# Mind-Synchronizing-Generator-PinHdrPotX.net
KiCad netlist of a schematic drawn in EAGLE
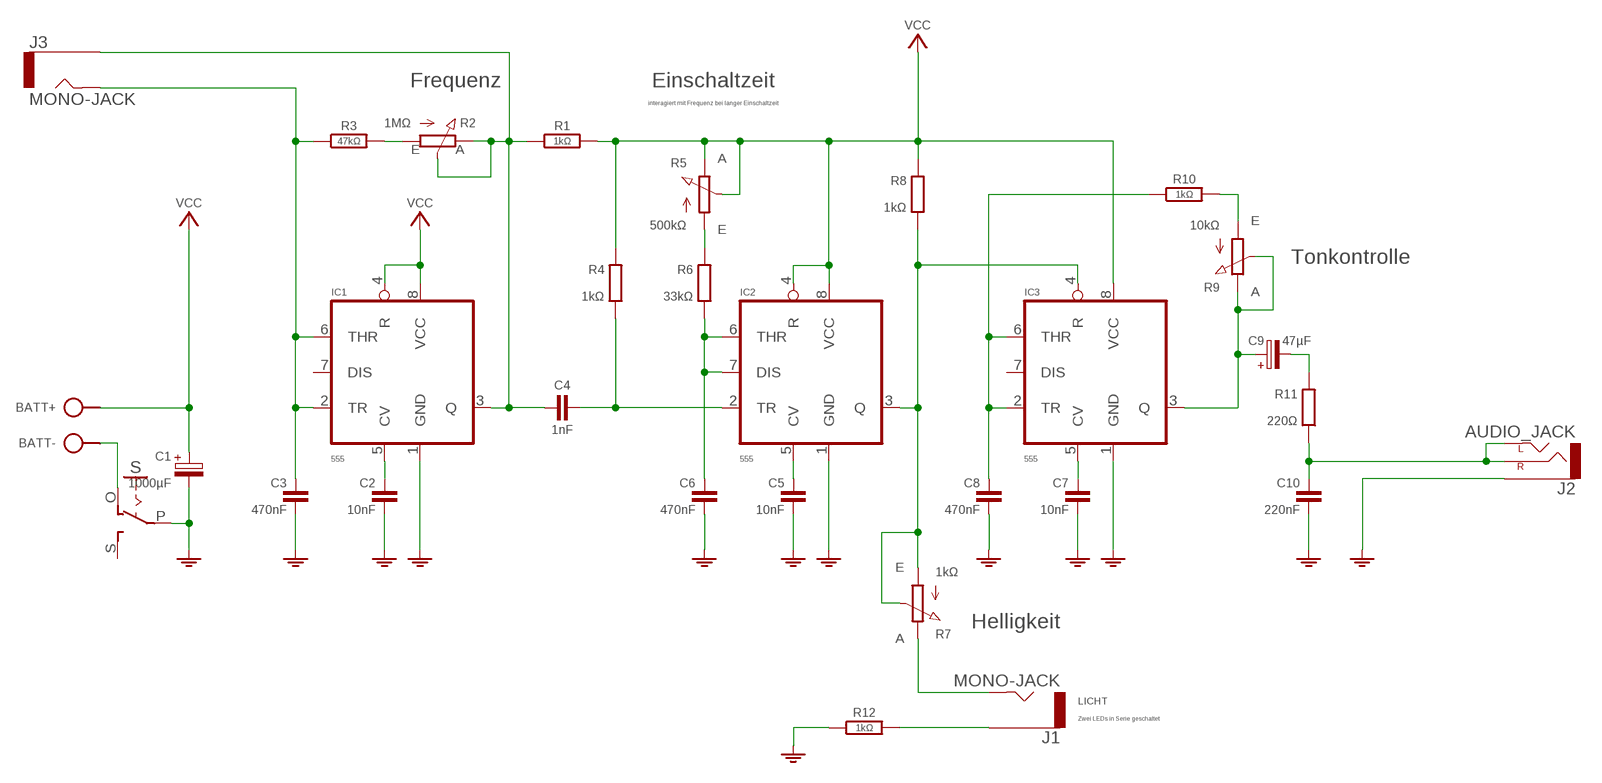
[diagram p0: schematic, sheet 1]

(export (version "E")
  (design (tool "Eeschema 10.0.6"))
  (components
    (comp (ref "BATT")
      (value "SPAD+--+")
      (footprint "eagle-import:SPAD-+")
      (libsource (lib "eagle-import") (part "SPAD+--+"))
    )
    (comp (ref "C1")
      (value "1000µF")
      (footprint "eagle-import:E2,5-6")
      (libsource (lib "eagle-import") (part "CPOLE2.5-6"))
    )
    (comp (ref "C2")
      (value "10nF")
      (footprint "eagle-import:C050-020X044")
      (libsource (lib "eagle-import") (part "C050-020X044"))
    )
    (comp (ref "C3")
      (value "470nF")
      (footprint "eagle-import:C050-040X075")
      (libsource (lib "eagle-import") (part "C050-040X075"))
    )
    (comp (ref "C4")
      (value "1nF")
      (footprint "eagle-import:C050-020X044")
      (libsource (lib "eagle-import") (part "C-H050-020X044"))
    )
    (comp (ref "C5")
      (value "10nF")
      (footprint "eagle-import:C050-020X044_V")
      (libsource (lib "eagle-import") (part "C050-020X044/V"))
    )
    (comp (ref "C6")
      (value "470nF")
      (footprint "eagle-import:C050-040X075")
      (libsource (lib "eagle-import") (part "C050-040X075"))
    )
    (comp (ref "C7")
      (value "10nF")
      (footprint "eagle-import:C075-020X044_V")
      (libsource (lib "eagle-import") (part "C075-020X044/V"))
    )
    (comp (ref "C8")
      (value "470nF")
      (footprint "eagle-import:C050-040X075")
      (libsource (lib "eagle-import") (part "C050-040X075"))
    )
    (comp (ref "C9")
      (value "47µF")
      (footprint "eagle-import:E2,5-4")
      (libsource (lib "eagle-import") (part "CPOL-HE2,5-4"))
    )
    (comp (ref "C10")
      (value "220nF")
      (footprint "eagle-import:C050-025X060")
      (libsource (lib "eagle-import") (part "C025-025X060"))
    )
    (comp (ref "IC1")
      (value "555")
      (footprint "eagle-import:555-DIL")
      (libsource (lib "eagle-import") (part "555_ALT2-LBL"))
    )
    (comp (ref "IC2")
      (value "555")
      (footprint "eagle-import:555-DIL")
      (libsource (lib "eagle-import") (part "555_ALT2-LBL"))
    )
    (comp (ref "IC3")
      (value "555")
      (footprint "eagle-import:555-DIL")
      (libsource (lib "eagle-import") (part "555_ALT2-LBL"))
    )
    (comp (ref "J1")
      (value "MONO-JACK")
      (footprint "eagle-import:STEREOJACK2.5MM_STEREOJACK2.5MM")
      (libsource (lib "eagle-import") (part "MONO-JACK"))
    )
    (comp (ref "J2")
      (value "AUDIO_JACK")
      (footprint "eagle-import:AUDIO-JACK")
      (libsource (lib "eagle-import") (part "AUDIO_JACK"))
    )
    (comp (ref "J3")
      (value "MONO-JACK")
      (footprint "eagle-import:STEREOJACK2.5MM_STEREOJACK2.5MM")
      (libsource (lib "eagle-import") (part "MONO-JACK"))
    )
    (comp (ref "R1")
      (value "1kΩ")
      (footprint "eagle-import:0204_10")
      (libsource (lib "eagle-import") (part "R-H0204/10"))
    )
    (comp (ref "R2")
      (value "1MΩ")
      (footprint "eagle-import:CONN-3P")
      (libsource (lib "eagle-import") (part "POT-H-3P"))
    )
    (comp (ref "R3")
      (value "47kΩ")
      (footprint "eagle-import:0204_10")
      (libsource (lib "eagle-import") (part "R-H0204/10"))
    )
    (comp (ref "R4")
      (value "1kΩ")
      (footprint "eagle-import:0204_10-V")
      (libsource (lib "eagle-import") (part "R0204/10-V"))
    )
    (comp (ref "R5")
      (value "500kΩ")
      (footprint "eagle-import:CONN-3P")
      (libsource (lib "eagle-import") (part "POT-3P"))
    )
    (comp (ref "R6")
      (value "33kΩ")
      (footprint "eagle-import:0204_10")
      (libsource (lib "eagle-import") (part "R0204/10"))
    )
    (comp (ref "R7")
      (value "1kΩ")
      (footprint "eagle-import:CONN-3P")
      (libsource (lib "eagle-import") (part "POT-3P-S1"))
    )
    (comp (ref "R8")
      (value "1kΩ")
      (footprint "eagle-import:0204_10-V")
      (libsource (lib "eagle-import") (part "R0204/10-V"))
    )
    (comp (ref "R9")
      (value "10kΩ")
      (footprint "eagle-import:CONN-3P")
      (libsource (lib "eagle-import") (part "POT-3P"))
    )
    (comp (ref "R10")
      (value "1kΩ")
      (footprint "eagle-import:0204_10")
      (libsource (lib "eagle-import") (part "R-H0204/10"))
    )
    (comp (ref "R11")
      (value "220Ω")
      (footprint "eagle-import:0204_10-V")
      (libsource (lib "eagle-import") (part "R0204/10-V"))
    )
    (comp (ref "R12")
      (value "1kΩ")
      (footprint "eagle-import:0204_10")
      (libsource (lib "eagle-import") (part "R-H0204/10"))
    )
    (comp (ref "S")
      (value "SL-SW-1P-2T-H")
      (footprint "eagle-import:SLSW-1P2T-H")
      (libsource (lib "eagle-import") (part "SL-SW-1P-2T-H"))
    )
  )
  (nets
    (net (code "1") (name "GND") (class "Default")
      (node (ref "C1") (pin "-") (pinfunction "-_-") (pintype "passive"))
      (node (ref "C10") (pin "2") (pinfunction "2_2") (pintype "passive"))
      (node (ref "C2") (pin "2") (pinfunction "2_2") (pintype "passive"))
      (node (ref "C3") (pin "2") (pinfunction "2_2") (pintype "passive"))
      (node (ref "C5") (pin "2") (pinfunction "2_2") (pintype "passive"))
      (node (ref "C6") (pin "2") (pinfunction "2_2") (pintype "passive"))
      (node (ref "C7") (pin "2") (pinfunction "2_2") (pintype "passive"))
      (node (ref "C8") (pin "2") (pinfunction "2_2") (pintype "passive"))
      (node (ref "IC1") (pin "1") (pinfunction "GND_1") (pintype "power_in"))
      (node (ref "IC2") (pin "1") (pinfunction "GND_1") (pintype "power_in"))
      (node (ref "IC3") (pin "1") (pinfunction "GND_1") (pintype "power_in"))
      (node (ref "J2") (pin "SLEEVE") (pinfunction "SLEEVE_SLEEVE") (pintype "bidirectional"))
      (node (ref "R12") (pin "1") (pinfunction "1_1") (pintype "passive"))
      (node (ref "S") (pin "P") (pinfunction "P_P") (pintype "passive"))
    )
    (net (code "2") (name "Net-(BATTB-P$1)") (class "Default")
      (node (ref "BATT") (pin "1") (pinfunction "P$1_1") (pintype "passive"))
      (node (ref "S") (pin "O") (pinfunction "O_O") (pintype "passive"))
    )
    (net (code "3") (name "Net-(IC1-CV)") (class "Default")
      (node (ref "C2") (pin "1") (pinfunction "1_1") (pintype "passive"))
      (node (ref "IC1") (pin "5") (pinfunction "CV_5") (pintype "input"))
    )
    (net (code "4") (name "Net-(IC1-Q)") (class "Default")
      (node (ref "C4") (pin "1") (pinfunction "1_1") (pintype "passive"))
      (node (ref "IC1") (pin "3") (pinfunction "Q_3") (pintype "output"))
      (node (ref "J3") (pin "SHIELD") (pinfunction "SLEEVE_SHIELD") (pintype "bidirectional"))
      (node (ref "R1") (pin "1") (pinfunction "1_1") (pintype "passive"))
      (node (ref "R2") (pin "2") (pinfunction "S_2") (pintype "passive"))
      (node (ref "R2") (pin "3") (pinfunction "E_3") (pintype "passive"))
    )
    (net (code "5") (name "Net-(IC1-THR)") (class "Default")
      (node (ref "C3") (pin "1") (pinfunction "1_1") (pintype "passive"))
      (node (ref "IC1") (pin "2") (pinfunction "TR_2") (pintype "input"))
      (node (ref "IC1") (pin "6") (pinfunction "THR_6") (pintype "input"))
      (node (ref "J3") (pin "TIP") (pinfunction "LEFT_TIP") (pintype "bidirectional"))
      (node (ref "R3") (pin "1") (pinfunction "1_1") (pintype "passive"))
    )
    (net (code "6") (name "Net-(IC2-CV)") (class "Default")
      (node (ref "C5") (pin "1") (pinfunction "1_1") (pintype "passive"))
      (node (ref "IC2") (pin "5") (pinfunction "CV_5") (pintype "input"))
    )
    (net (code "7") (name "Net-(IC2-DIS)") (class "Default")
      (node (ref "C6") (pin "1") (pinfunction "1_1") (pintype "passive"))
      (node (ref "IC2") (pin "6") (pinfunction "THR_6") (pintype "input"))
      (node (ref "IC2") (pin "7") (pinfunction "DIS_7") (pintype "passive"))
      (node (ref "R6") (pin "2") (pinfunction "1_2") (pintype "passive"))
    )
    (net (code "8") (name "Net-(IC2-Q)") (class "Default")
      (node (ref "IC2") (pin "3") (pinfunction "Q_3") (pintype "output"))
      (node (ref "IC3") (pin "4") (pinfunction "R_4") (pintype "input"))
      (node (ref "R7") (pin "1") (pinfunction "S_1") (pintype "passive"))
      (node (ref "R7") (pin "2") (pinfunction "A_2") (pintype "passive"))
      (node (ref "R8") (pin "2") (pinfunction "1_2") (pintype "passive"))
    )
    (net (code "9") (name "Net-(IC2-TR)") (class "Default")
      (node (ref "C4") (pin "2") (pinfunction "2_2") (pintype "passive"))
      (node (ref "IC2") (pin "2") (pinfunction "TR_2") (pintype "input"))
      (node (ref "R4") (pin "2") (pinfunction "1_2") (pintype "passive"))
    )
    (net (code "10") (name "Net-(IC3-CV)") (class "Default")
      (node (ref "C7") (pin "1") (pinfunction "1_1") (pintype "passive"))
      (node (ref "IC3") (pin "5") (pinfunction "CV_5") (pintype "input"))
    )
    (net (code "11") (name "Net-(IC3-Q)") (class "Default")
      (node (ref "C9") (pin "+") (pinfunction "+_+") (pintype "passive"))
      (node (ref "IC3") (pin "3") (pinfunction "Q_3") (pintype "output"))
      (node (ref "R9") (pin "2") (pinfunction "S_2") (pintype "passive"))
      (node (ref "R9") (pin "3") (pinfunction "E_3") (pintype "passive"))
    )
    (net (code "12") (name "Net-(IC3-THR)") (class "Default")
      (node (ref "C8") (pin "1") (pinfunction "1_1") (pintype "passive"))
      (node (ref "IC3") (pin "2") (pinfunction "TR_2") (pintype "input"))
      (node (ref "IC3") (pin "6") (pinfunction "THR_6") (pintype "input"))
      (node (ref "R10") (pin "1") (pinfunction "1_1") (pintype "passive"))
    )
    (net (code "13") (name "Net-(J1-LEFT)") (class "Default")
      (node (ref "J1") (pin "TIP") (pinfunction "LEFT_TIP") (pintype "bidirectional"))
      (node (ref "R7") (pin "3") (pinfunction "E_3") (pintype "passive"))
    )
    (net (code "14") (name "Net-(J1-SLEEVE)") (class "Default")
      (node (ref "J1") (pin "SHIELD") (pinfunction "SLEEVE_SHIELD") (pintype "bidirectional"))
      (node (ref "R12") (pin "2") (pinfunction "2_2") (pintype "passive"))
    )
    (net (code "15") (name "Net-(J2-LEFT)") (class "Default")
      (node (ref "C10") (pin "1") (pinfunction "1_1") (pintype "passive"))
      (node (ref "J2") (pin "RING") (pinfunction "RIGHT_RING") (pintype "bidirectional"))
      (node (ref "J2") (pin "TIP") (pinfunction "LEFT_TIP") (pintype "bidirectional"))
      (node (ref "R11") (pin "2") (pinfunction "1_2") (pintype "passive"))
    )
    (net (code "16") (name "Net-(R2-A)") (class "Default")
      (node (ref "R2") (pin "1") (pinfunction "A_1") (pintype "passive"))
      (node (ref "R3") (pin "2") (pinfunction "2_2") (pintype "passive"))
    )
    (net (code "17") (name "Net-(R5-A)") (class "Default")
      (node (ref "R5") (pin "1") (pinfunction "A_1") (pintype "passive"))
      (node (ref "R6") (pin "1") (pinfunction "2_1") (pintype "passive"))
    )
    (net (code "18") (name "Net-(R9-A)") (class "Default")
      (node (ref "R10") (pin "2") (pinfunction "2_2") (pintype "passive"))
      (node (ref "R9") (pin "1") (pinfunction "A_1") (pintype "passive"))
    )
    (net (code "19") (name "Net-(R11-2)") (class "Default")
      (node (ref "C9") (pin "-") (pinfunction "-_-") (pintype "passive"))
      (node (ref "R11") (pin "1") (pinfunction "2_1") (pintype "passive"))
    )
    (net (code "20") (name "VCC") (class "Default")
      (node (ref "BATT") (pin "2") (pinfunction "P$1_2") (pintype "passive"))
      (node (ref "C1") (pin "+") (pinfunction "+_+") (pintype "passive"))
      (node (ref "IC1") (pin "4") (pinfunction "R_4") (pintype "input"))
      (node (ref "IC1") (pin "8") (pinfunction "VCC_8") (pintype "power_in"))
      (node (ref "IC2") (pin "4") (pinfunction "R_4") (pintype "input"))
      (node (ref "IC2") (pin "8") (pinfunction "VCC_8") (pintype "power_in"))
      (node (ref "IC3") (pin "8") (pinfunction "VCC_8") (pintype "power_in"))
      (node (ref "R1") (pin "2") (pinfunction "2_2") (pintype "passive"))
      (node (ref "R4") (pin "1") (pinfunction "2_1") (pintype "passive"))
      (node (ref "R5") (pin "2") (pinfunction "S_2") (pintype "passive"))
      (node (ref "R5") (pin "3") (pinfunction "E_3") (pintype "passive"))
      (node (ref "R8") (pin "1") (pinfunction "2_1") (pintype "passive"))
    )
    (net (code "21") (name "unconnected-(IC1-DIS-Pad7)") (class "Default")
      (node (ref "IC1") (pin "7") (pinfunction "DIS_7") (pintype "passive"))
    )
    (net (code "22") (name "unconnected-(IC3-DIS-Pad7)") (class "Default")
      (node (ref "IC3") (pin "7") (pinfunction "DIS_7") (pintype "passive"))
    )
    (net (code "23") (name "unconnected-(S-PadS)") (class "Default")
      (node (ref "S") (pin "S") (pinfunction "S_S") (pintype "passive"))
    )
  )
)
